# LED.net
KiCad netlist of a schematic drawn in Altium Designer
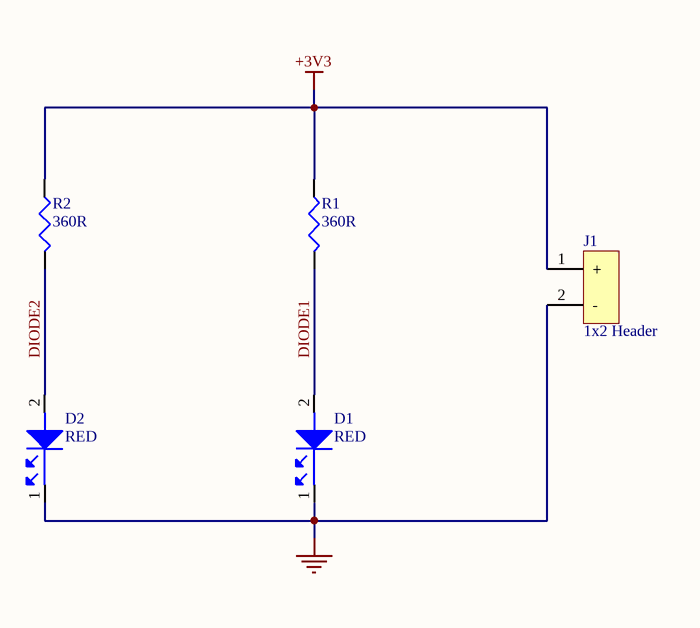
[diagram p0: LED.SchDoc]

(export (version "E")
  (design (tool "Eeschema 10.0.6"))
  (components
    (comp (ref "D1")
      (value "RED")
      (footprint "LED0803RED")
      (description "LED Uni-Color Red 643nm Automotive 2-Pin SMD T/R")
      (fields
        (field (name "MANUFACTURER") "Osram Opto")
        (field (name "MANUFACTURER PART NUMBER") "LSL29K-G1J2-1-Z")
      )
      (libsource (lib "LED") (part "LSL29K-G1J2-1-Z"))
    )
    (comp (ref "D2")
      (value "RED")
      (footprint "LED0803RED")
      (description "LED Uni-Color Red 643nm Automotive 2-Pin SMD T/R")
      (fields
        (field (name "MANUFACTURER") "Osram Opto")
        (field (name "MANUFACTURER PART NUMBER") "LSL29K-G1J2-1-Z")
      )
      (libsource (lib "LED") (part "LSL29K-G1J2-1-Z"))
    )
    (comp (ref "J1")
      (value "1x2 Header")
      (footprint "HDR1X2")
      (fields (field (name "MANUFACTURER") "Molex") (field (name "MANUFACTURER PART NUMBER") "022292021"))
      (libsource (lib "LED") (part "022292021"))
    )
    (comp (ref "R1")
      (value "360R")
      (footprint "R0805")
      (fields
        (field (name "TOLERANCE") "1%")
        (field (name "MANUFACTURER") "Vishay")
        (field (name "MANUFACTURER PART NUMBER") "CRCW080536R0FKEA")
      )
      (libsource (lib "LED") (part "CRCW080536R0FKEA"))
    )
    (comp (ref "R2")
      (value "360R")
      (footprint "R0805")
      (fields
        (field (name "TOLERANCE") "1%")
        (field (name "MANUFACTURER") "Vishay")
        (field (name "MANUFACTURER PART NUMBER") "CRCW080536R0FKEA")
      )
      (libsource (lib "LED") (part "CRCW080536R0FKEA"))
    )
  )
  (nets
    (net (code "1") (name "+3V3") (class "Default")
      (node (ref "J1") (pin "1") (pinfunction "+_1") (pintype "passive"))
      (node (ref "R1") (pin "1") (pinfunction "1_1") (pintype "passive"))
      (node (ref "R2") (pin "1") (pinfunction "1_1") (pintype "passive"))
    )
    (net (code "2") (name "/DIODE1") (class "Default")
      (node (ref "D1") (pin "2") (pinfunction "2_2") (pintype "passive"))
      (node (ref "R1") (pin "2") (pinfunction "2_2") (pintype "passive"))
    )
    (net (code "3") (name "/DIODE2") (class "Default")
      (node (ref "D2") (pin "2") (pinfunction "2_2") (pintype "passive"))
      (node (ref "R2") (pin "2") (pinfunction "2_2") (pintype "passive"))
    )
    (net (code "4") (name "GND") (class "Default")
      (node (ref "D1") (pin "1") (pinfunction "RED_1") (pintype "passive"))
      (node (ref "D2") (pin "1") (pinfunction "RED_1") (pintype "passive"))
      (node (ref "J1") (pin "2") (pinfunction "-_2") (pintype "passive"))
    )
  )
)
